# Power.net
KiCad netlist of a schematic drawn in Altium Designer
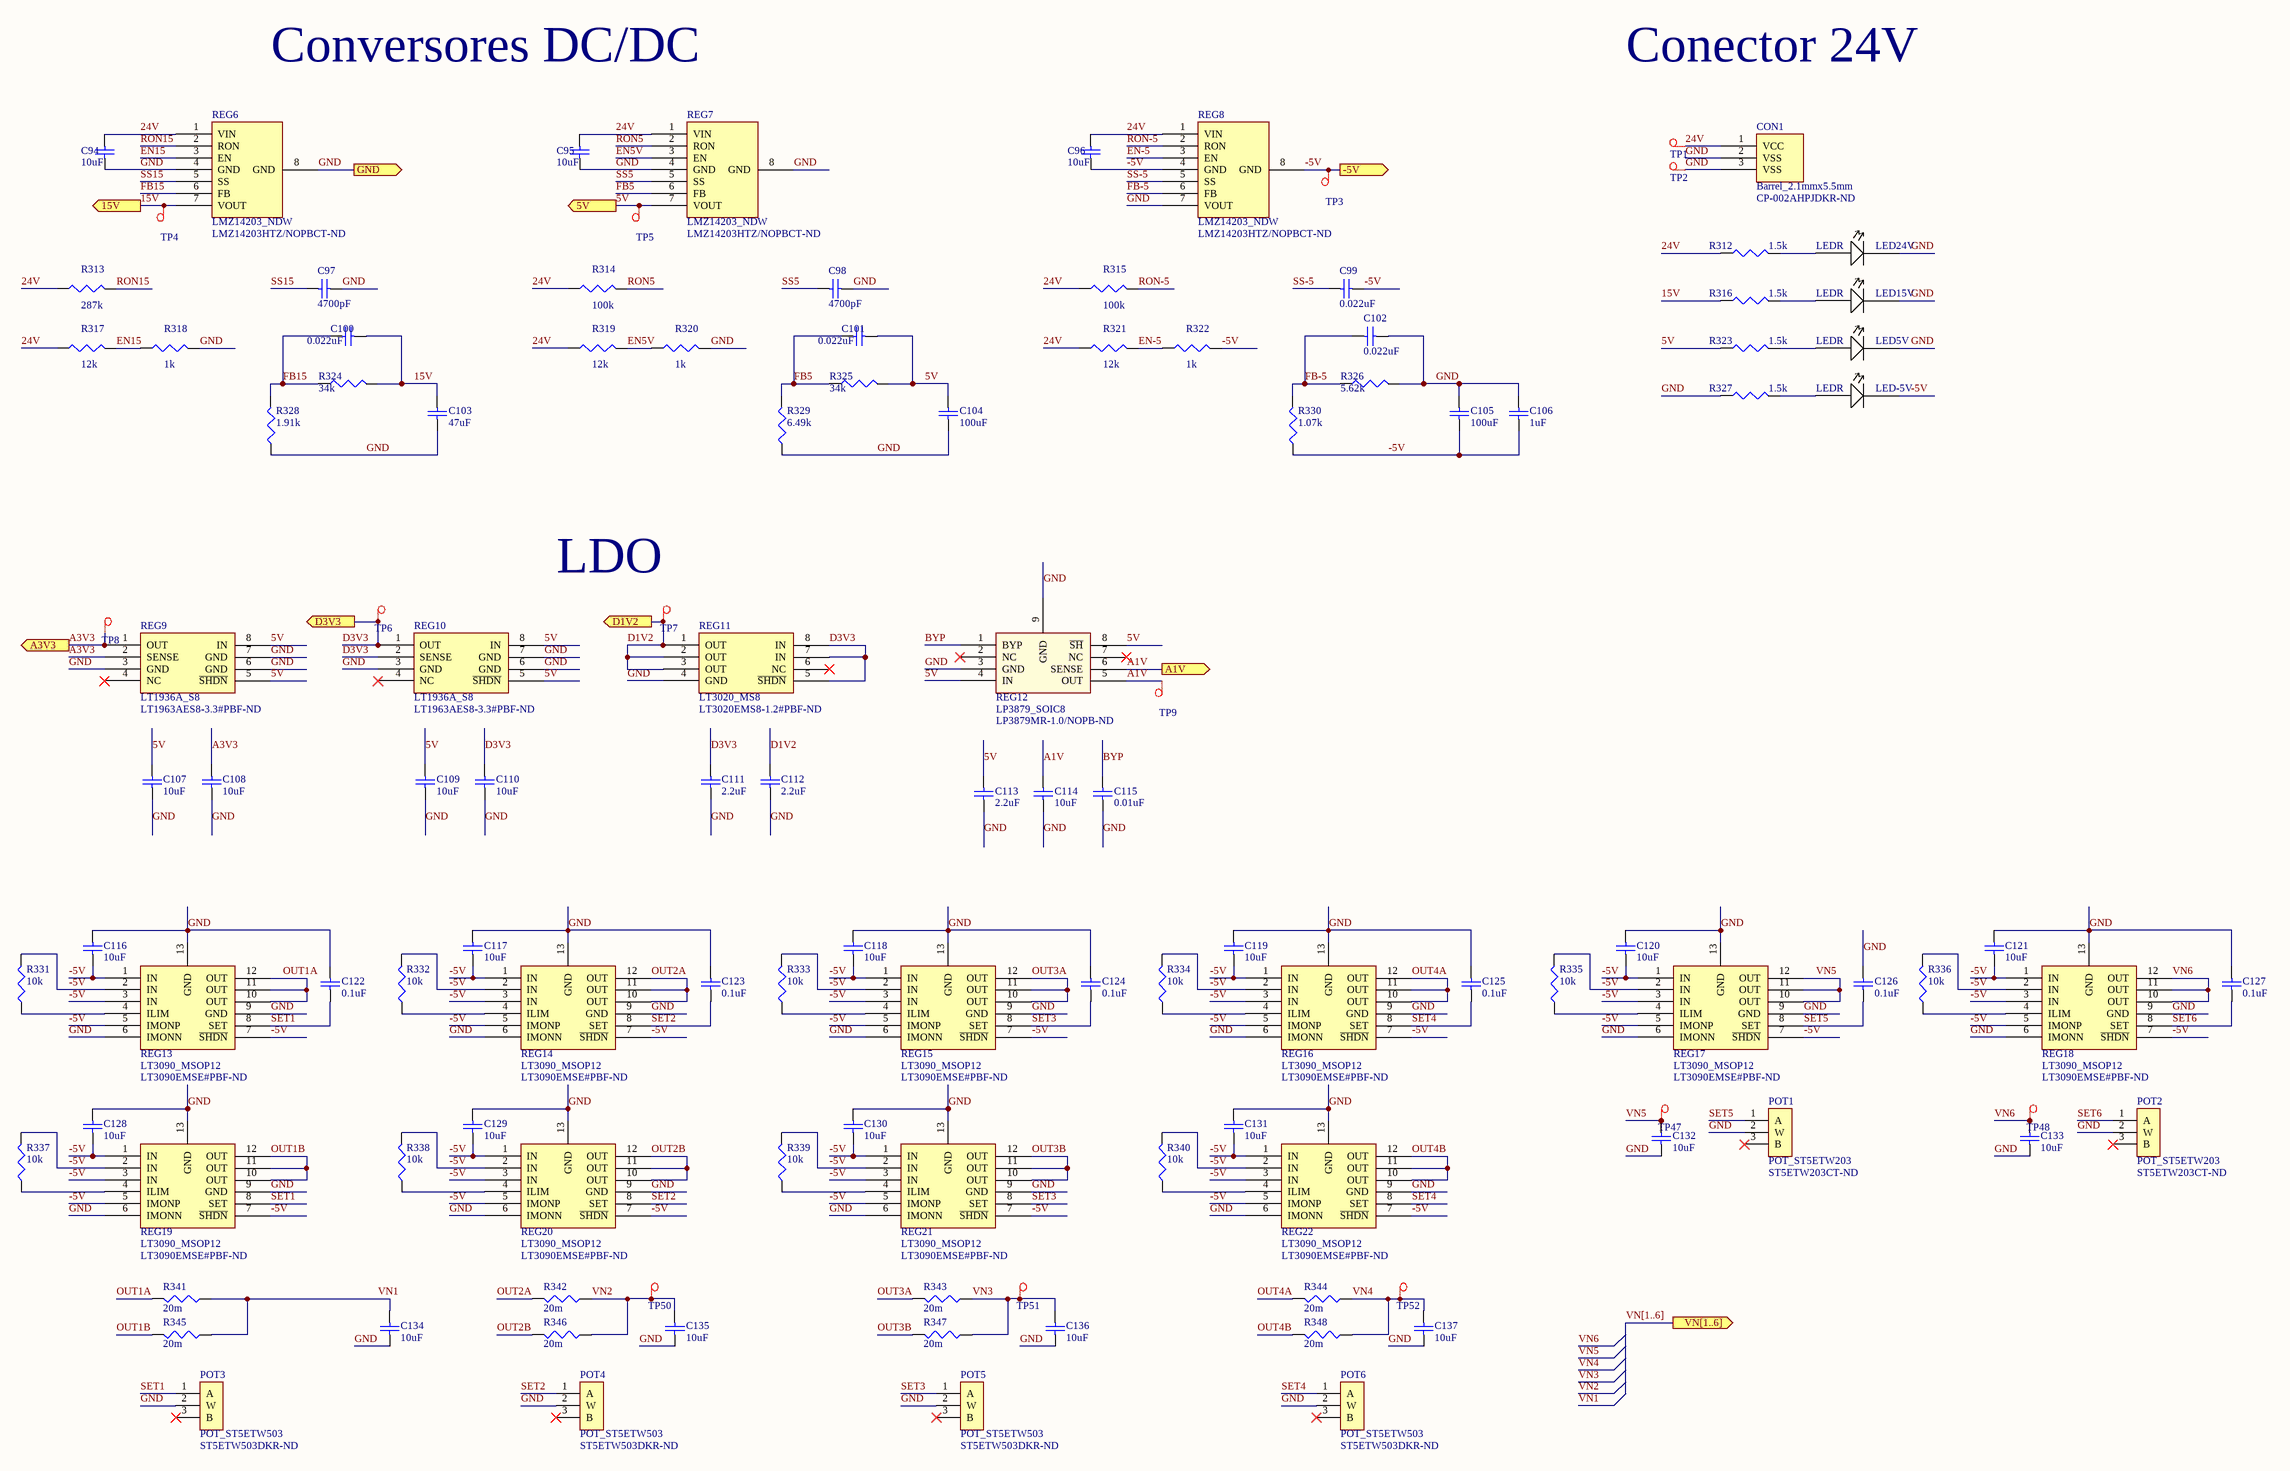
[diagram p0: Power.SchDoc]

(export (version "E")
  (design (tool "Eeschema 10.0.6"))
  (components
    (comp (ref "C94")
      (value "10uF")
      (footprint "RES_1206")
      (description "Capacitor")
      (fields (field (name "Comment") "Cap") (field (name "PUBLISHER") "Altium Limited"))
      (libsource (lib "Miscellaneous Devices") (part "Cap"))
    )
    (comp (ref "C95")
      (value "10uF")
      (footprint "RES_1206")
      (description "Capacitor")
      (fields (field (name "Comment") "Cap") (field (name "PUBLISHER") "Altium Limited"))
      (libsource (lib "Miscellaneous Devices") (part "Cap"))
    )
    (comp (ref "C96")
      (value "10uF")
      (footprint "RES_1206")
      (description "Capacitor")
      (fields (field (name "Comment") "Cap") (field (name "PUBLISHER") "Altium Limited"))
      (libsource (lib "Miscellaneous Devices") (part "Cap"))
    )
    (comp (ref "C97")
      (value "4700pF")
      (footprint "J1-0603")
      (description "Capacitor")
      (fields (field (name "Comment") "Cap") (field (name "PUBLISHER") "Altium Limited"))
      (libsource (lib "Miscellaneous Devices") (part "Cap"))
    )
    (comp (ref "C98")
      (value "4700pF")
      (footprint "J1-0603")
      (description "Capacitor")
      (fields (field (name "Comment") "Cap") (field (name "PUBLISHER") "Altium Limited"))
      (libsource (lib "Miscellaneous Devices") (part "Cap"))
    )
    (comp (ref "C99")
      (value "0.022uF")
      (footprint "J1-0603")
      (description "Capacitor")
      (fields (field (name "Comment") "Cap") (field (name "PUBLISHER") "Altium Limited"))
      (libsource (lib "Miscellaneous Devices") (part "Cap"))
    )
    (comp (ref "C100")
      (value "0.022uF")
      (footprint "J1-0603")
      (description "Capacitor")
      (fields (field (name "Comment") "Cap") (field (name "PUBLISHER") "Altium Limited"))
      (libsource (lib "Miscellaneous Devices") (part "Cap"))
    )
    (comp (ref "C101")
      (value "0.022uF")
      (footprint "J1-0603")
      (description "Capacitor")
      (fields (field (name "Comment") "Cap") (field (name "PUBLISHER") "Altium Limited"))
      (libsource (lib "Miscellaneous Devices") (part "Cap"))
    )
    (comp (ref "C102")
      (value "0.022uF")
      (footprint "J1-0603")
      (description "Capacitor")
      (fields (field (name "Comment") "Cap") (field (name "PUBLISHER") "Altium Limited"))
      (libsource (lib "Miscellaneous Devices") (part "Cap"))
    )
    (comp (ref "C103")
      (value "47uF")
      (footprint "RES_1206")
      (description "Capacitor")
      (fields (field (name "Comment") "Cap") (field (name "PUBLISHER") "Altium Limited"))
      (libsource (lib "Miscellaneous Devices") (part "Cap"))
    )
    (comp (ref "C104")
      (value "100uF")
      (footprint "J1-0603")
      (description "Capacitor")
      (fields (field (name "Comment") "Cap") (field (name "PUBLISHER") "Altium Limited"))
      (libsource (lib "Miscellaneous Devices") (part "Cap"))
    )
    (comp (ref "C105")
      (value "100uF")
      (footprint "J1-0603")
      (description "Capacitor")
      (fields (field (name "Comment") "Cap") (field (name "PUBLISHER") "Altium Limited"))
      (libsource (lib "Miscellaneous Devices") (part "Cap"))
    )
    (comp (ref "C106")
      (value "1uF")
      (footprint "J1-0603")
      (description "Capacitor")
      (fields (field (name "Comment") "Cap") (field (name "PUBLISHER") "Altium Limited"))
      (libsource (lib "Miscellaneous Devices") (part "Cap"))
    )
    (comp (ref "C107")
      (value "10uF")
      (footprint "RES_0805")
      (description "Capacitor")
      (fields (field (name "Comment") "Cap") (field (name "PUBLISHER") "Altium Limited"))
      (libsource (lib "Miscellaneous Devices") (part "Cap"))
    )
    (comp (ref "C108")
      (value "10uF")
      (footprint "RES_0805")
      (description "Capacitor")
      (fields (field (name "Comment") "Cap") (field (name "PUBLISHER") "Altium Limited"))
      (libsource (lib "Miscellaneous Devices") (part "Cap"))
    )
    (comp (ref "C109")
      (value "10uF")
      (footprint "RES_0805")
      (description "Capacitor")
      (fields (field (name "Comment") "Cap") (field (name "PUBLISHER") "Altium Limited"))
      (libsource (lib "Miscellaneous Devices") (part "Cap"))
    )
    (comp (ref "C110")
      (value "10uF")
      (footprint "RES_0805")
      (description "Capacitor")
      (fields (field (name "Comment") "Cap") (field (name "PUBLISHER") "Altium Limited"))
      (libsource (lib "Miscellaneous Devices") (part "Cap"))
    )
    (comp (ref "C111")
      (value "2.2uF")
      (footprint "J1-0603")
      (description "Capacitor")
      (fields (field (name "Comment") "Cap") (field (name "PUBLISHER") "Altium Limited"))
      (libsource (lib "Miscellaneous Devices") (part "Cap"))
    )
    (comp (ref "C112")
      (value "2.2uF")
      (footprint "J1-0603")
      (description "Capacitor")
      (fields (field (name "Comment") "Cap") (field (name "PUBLISHER") "Altium Limited"))
      (libsource (lib "Miscellaneous Devices") (part "Cap"))
    )
    (comp (ref "C113")
      (value "2.2uF")
      (footprint "J1-0603")
      (description "Capacitor")
      (fields (field (name "Comment") "Cap") (field (name "PUBLISHER") "Altium Limited"))
      (libsource (lib "Miscellaneous Devices") (part "Cap"))
    )
    (comp (ref "C114")
      (value "10uF")
      (footprint "RES_0805")
      (description "Capacitor")
      (fields (field (name "Comment") "Cap") (field (name "PUBLISHER") "Altium Limited"))
      (libsource (lib "Miscellaneous Devices") (part "Cap"))
    )
    (comp (ref "C115")
      (value "0.01uF")
      (footprint "J1-0603")
      (description "Capacitor")
      (fields (field (name "Comment") "Cap") (field (name "PUBLISHER") "Altium Limited"))
      (libsource (lib "Miscellaneous Devices") (part "Cap"))
    )
    (comp (ref "C116")
      (value "10uF")
      (footprint "RES_0805")
      (description "Capacitor")
      (fields (field (name "Comment") "Cap") (field (name "PUBLISHER") "Altium Limited"))
      (libsource (lib "Miscellaneous Devices") (part "Cap"))
    )
    (comp (ref "C117")
      (value "10uF")
      (footprint "RES_0805")
      (description "Capacitor")
      (fields (field (name "Comment") "Cap") (field (name "PUBLISHER") "Altium Limited"))
      (libsource (lib "Miscellaneous Devices") (part "Cap"))
    )
    (comp (ref "C118")
      (value "10uF")
      (footprint "RES_0805")
      (description "Capacitor")
      (fields (field (name "Comment") "Cap") (field (name "PUBLISHER") "Altium Limited"))
      (libsource (lib "Miscellaneous Devices") (part "Cap"))
    )
    (comp (ref "C119")
      (value "10uF")
      (footprint "RES_0805")
      (description "Capacitor")
      (fields (field (name "Comment") "Cap") (field (name "PUBLISHER") "Altium Limited"))
      (libsource (lib "Miscellaneous Devices") (part "Cap"))
    )
    (comp (ref "C120")
      (value "10uF")
      (footprint "RES_0805")
      (description "Capacitor")
      (fields (field (name "Comment") "Cap") (field (name "PUBLISHER") "Altium Limited"))
      (libsource (lib "Miscellaneous Devices") (part "Cap"))
    )
    (comp (ref "C121")
      (value "10uF")
      (footprint "RES_0805")
      (description "Capacitor")
      (fields (field (name "Comment") "Cap") (field (name "PUBLISHER") "Altium Limited"))
      (libsource (lib "Miscellaneous Devices") (part "Cap"))
    )
    (comp (ref "C122")
      (value "0.1uF")
      (footprint "J1-0603")
      (description "Capacitor")
      (fields (field (name "Comment") "Cap") (field (name "PUBLISHER") "Altium Limited"))
      (libsource (lib "Miscellaneous Devices") (part "Cap"))
    )
    (comp (ref "C123")
      (value "0.1uF")
      (footprint "J1-0603")
      (description "Capacitor")
      (fields (field (name "Comment") "Cap") (field (name "PUBLISHER") "Altium Limited"))
      (libsource (lib "Miscellaneous Devices") (part "Cap"))
    )
    (comp (ref "C124")
      (value "0.1uF")
      (footprint "J1-0603")
      (description "Capacitor")
      (fields (field (name "Comment") "Cap") (field (name "PUBLISHER") "Altium Limited"))
      (libsource (lib "Miscellaneous Devices") (part "Cap"))
    )
    (comp (ref "C125")
      (value "0.1uF")
      (footprint "J1-0603")
      (description "Capacitor")
      (fields (field (name "Comment") "Cap") (field (name "PUBLISHER") "Altium Limited"))
      (libsource (lib "Miscellaneous Devices") (part "Cap"))
    )
    (comp (ref "C126")
      (value "0.1uF")
      (footprint "J1-0603")
      (description "Capacitor")
      (fields (field (name "Comment") "Cap") (field (name "PUBLISHER") "Altium Limited"))
      (libsource (lib "Miscellaneous Devices") (part "Cap"))
    )
    (comp (ref "C127")
      (value "0.1uF")
      (footprint "J1-0603")
      (description "Capacitor")
      (fields (field (name "Comment") "Cap") (field (name "PUBLISHER") "Altium Limited"))
      (libsource (lib "Miscellaneous Devices") (part "Cap"))
    )
    (comp (ref "C128")
      (value "10uF")
      (footprint "RES_0805")
      (description "Capacitor")
      (fields (field (name "Comment") "Cap") (field (name "PUBLISHER") "Altium Limited"))
      (libsource (lib "Miscellaneous Devices") (part "Cap"))
    )
    (comp (ref "C129")
      (value "10uF")
      (footprint "RES_0805")
      (description "Capacitor")
      (fields (field (name "Comment") "Cap") (field (name "PUBLISHER") "Altium Limited"))
      (libsource (lib "Miscellaneous Devices") (part "Cap"))
    )
    (comp (ref "C130")
      (value "10uF")
      (footprint "RES_0805")
      (description "Capacitor")
      (fields (field (name "Comment") "Cap") (field (name "PUBLISHER") "Altium Limited"))
      (libsource (lib "Miscellaneous Devices") (part "Cap"))
    )
    (comp (ref "C131")
      (value "10uF")
      (footprint "RES_0805")
      (description "Capacitor")
      (fields (field (name "Comment") "Cap") (field (name "PUBLISHER") "Altium Limited"))
      (libsource (lib "Miscellaneous Devices") (part "Cap"))
    )
    (comp (ref "C132")
      (value "10uF")
      (footprint "RES_0805")
      (description "Capacitor")
      (fields (field (name "Comment") "Cap") (field (name "PUBLISHER") "Altium Limited"))
      (libsource (lib "Miscellaneous Devices") (part "Cap"))
    )
    (comp (ref "C133")
      (value "10uF")
      (footprint "RES_0805")
      (description "Capacitor")
      (fields (field (name "Comment") "Cap") (field (name "PUBLISHER") "Altium Limited"))
      (libsource (lib "Miscellaneous Devices") (part "Cap"))
    )
    (comp (ref "C134")
      (value "10uF")
      (footprint "RES_0805")
      (description "Capacitor")
      (fields (field (name "Comment") "Cap") (field (name "PUBLISHER") "Altium Limited"))
      (libsource (lib "Miscellaneous Devices") (part "Cap"))
    )
    (comp (ref "C135")
      (value "10uF")
      (footprint "RES_0805")
      (description "Capacitor")
      (fields (field (name "Comment") "Cap") (field (name "PUBLISHER") "Altium Limited"))
      (libsource (lib "Miscellaneous Devices") (part "Cap"))
    )
    (comp (ref "C136")
      (value "10uF")
      (footprint "RES_0805")
      (description "Capacitor")
      (fields (field (name "Comment") "Cap") (field (name "PUBLISHER") "Altium Limited"))
      (libsource (lib "Miscellaneous Devices") (part "Cap"))
    )
    (comp (ref "C137")
      (value "10uF")
      (footprint "RES_0805")
      (description "Capacitor")
      (fields (field (name "Comment") "Cap") (field (name "PUBLISHER") "Altium Limited"))
      (libsource (lib "Miscellaneous Devices") (part "Cap"))
    )
    (comp (ref "CON1")
      (value "Barrel_2.1mmx5.5mm")
      (footprint "Barrel_2.1mmx5.5mm")
      (fields (field (name "SUPPLIER PART NUMBER 1") "CP-002AHPJDKR-ND"))
      (libsource (lib "Lib1") (part "Barrel_2.1mmx5.5mm"))
    )
    (comp (ref "LED-5V") (value "LEDR") (footprint "LED") (libsource (lib "Lib1") (part "LEDR")))
    (comp (ref "LED5V") (value "LEDR") (footprint "LED") (libsource (lib "Lib1") (part "LEDR")))
    (comp (ref "LED15V") (value "LEDR") (footprint "LED") (libsource (lib "Lib1") (part "LEDR")))
    (comp (ref "LED24V") (value "LEDR") (footprint "LED") (libsource (lib "Lib1") (part "LEDR")))
    (comp (ref "POT1")
      (value "POT_ST5ETW203")
      (footprint "POT_ST5ETW")
      (fields (field (name "SUPPLIER PART NUMBER 1") "ST5ETW203CT-ND"))
      (libsource (lib "Lib1") (part "POT_ST5ETW203"))
    )
    (comp (ref "POT2")
      (value "POT_ST5ETW203")
      (footprint "POT_ST5ETW")
      (fields (field (name "SUPPLIER PART NUMBER 1") "ST5ETW203CT-ND"))
      (libsource (lib "Lib1") (part "POT_ST5ETW203"))
    )
    (comp (ref "POT3")
      (value "POT_ST5ETW503")
      (footprint "POT_ST5ETW")
      (fields (field (name "SUPPLIER PART NUMBER 1") "ST5ETW503DKR-ND"))
      (libsource (lib "Lib1") (part "POT_ST5ETW503"))
    )
    (comp (ref "POT4")
      (value "POT_ST5ETW503")
      (footprint "POT_ST5ETW")
      (fields (field (name "SUPPLIER PART NUMBER 1") "ST5ETW503DKR-ND"))
      (libsource (lib "Lib1") (part "POT_ST5ETW503"))
    )
    (comp (ref "POT5")
      (value "POT_ST5ETW503")
      (footprint "POT_ST5ETW")
      (fields (field (name "SUPPLIER PART NUMBER 1") "ST5ETW503DKR-ND"))
      (libsource (lib "Lib1") (part "POT_ST5ETW503"))
    )
    (comp (ref "POT6")
      (value "POT_ST5ETW503")
      (footprint "POT_ST5ETW")
      (fields (field (name "SUPPLIER PART NUMBER 1") "ST5ETW503DKR-ND"))
      (libsource (lib "Lib1") (part "POT_ST5ETW503"))
    )
    (comp (ref "R312")
      (value "1.5k")
      (footprint "J1-0603")
      (description "Resistor")
      (fields (field (name "Comment") "Res3") (field (name "PUBLISHER") "Altium Limited"))
      (libsource (lib "Miscellaneous Devices") (part "Res3"))
    )
    (comp (ref "R313")
      (value "287k")
      (footprint "J1-0603")
      (description "Resistor")
      (fields (field (name "Comment") "Res3") (field (name "PUBLISHER") "Altium Limited"))
      (libsource (lib "Miscellaneous Devices") (part "Res3"))
    )
    (comp (ref "R314")
      (value "100k")
      (footprint "J1-0603")
      (description "Resistor")
      (fields (field (name "Comment") "Res3") (field (name "PUBLISHER") "Altium Limited"))
      (libsource (lib "Miscellaneous Devices") (part "Res3"))
    )
    (comp (ref "R315")
      (value "100k")
      (footprint "J1-0603")
      (description "Resistor")
      (fields (field (name "Comment") "Res3") (field (name "PUBLISHER") "Altium Limited"))
      (libsource (lib "Miscellaneous Devices") (part "Res3"))
    )
    (comp (ref "R316")
      (value "1.5k")
      (footprint "J1-0603")
      (description "Resistor")
      (fields (field (name "Comment") "Res3") (field (name "PUBLISHER") "Altium Limited"))
      (libsource (lib "Miscellaneous Devices") (part "Res3"))
    )
    (comp (ref "R317")
      (value "12k")
      (footprint "J1-0603")
      (description "Resistor")
      (fields (field (name "Comment") "Res3") (field (name "PUBLISHER") "Altium Limited"))
      (libsource (lib "Miscellaneous Devices") (part "Res3"))
    )
    (comp (ref "R318")
      (value "1k")
      (footprint "J1-0603")
      (description "Resistor")
      (fields (field (name "Comment") "Res3") (field (name "PUBLISHER") "Altium Limited"))
      (libsource (lib "Miscellaneous Devices") (part "Res3"))
    )
    (comp (ref "R319")
      (value "12k")
      (footprint "J1-0603")
      (description "Resistor")
      (fields (field (name "Comment") "Res3") (field (name "PUBLISHER") "Altium Limited"))
      (libsource (lib "Miscellaneous Devices") (part "Res3"))
    )
    (comp (ref "R320")
      (value "1k")
      (footprint "J1-0603")
      (description "Resistor")
      (fields (field (name "Comment") "Res3") (field (name "PUBLISHER") "Altium Limited"))
      (libsource (lib "Miscellaneous Devices") (part "Res3"))
    )
    (comp (ref "R321")
      (value "12k")
      (footprint "J1-0603")
      (description "Resistor")
      (fields (field (name "Comment") "Res3") (field (name "PUBLISHER") "Altium Limited"))
      (libsource (lib "Miscellaneous Devices") (part "Res3"))
    )
    (comp (ref "R322")
      (value "1k")
      (footprint "J1-0603")
      (description "Resistor")
      (fields (field (name "Comment") "Res3") (field (name "PUBLISHER") "Altium Limited"))
      (libsource (lib "Miscellaneous Devices") (part "Res3"))
    )
    (comp (ref "R323")
      (value "1.5k")
      (footprint "J1-0603")
      (description "Resistor")
      (fields (field (name "Comment") "Res3") (field (name "PUBLISHER") "Altium Limited"))
      (libsource (lib "Miscellaneous Devices") (part "Res3"))
    )
    (comp (ref "R324")
      (value "34k")
      (footprint "J1-0603")
      (description "Resistor")
      (fields (field (name "Comment") "Res3") (field (name "PUBLISHER") "Altium Limited"))
      (libsource (lib "Miscellaneous Devices") (part "Res3"))
    )
    (comp (ref "R325")
      (value "34k")
      (footprint "J1-0603")
      (description "Resistor")
      (fields (field (name "Comment") "Res3") (field (name "PUBLISHER") "Altium Limited"))
      (libsource (lib "Miscellaneous Devices") (part "Res3"))
    )
    (comp (ref "R326")
      (value "5.62k")
      (footprint "J1-0603")
      (description "Resistor")
      (fields (field (name "Comment") "Res3") (field (name "PUBLISHER") "Altium Limited"))
      (libsource (lib "Miscellaneous Devices") (part "Res3"))
    )
    (comp (ref "R327")
      (value "1.5k")
      (footprint "J1-0603")
      (description "Resistor")
      (fields (field (name "Comment") "Res3") (field (name "PUBLISHER") "Altium Limited"))
      (libsource (lib "Miscellaneous Devices") (part "Res3"))
    )
    (comp (ref "R328")
      (value "1.91k")
      (footprint "J1-0603")
      (description "Resistor")
      (fields (field (name "Comment") "Res3") (field (name "PUBLISHER") "Altium Limited"))
      (libsource (lib "Miscellaneous Devices") (part "Res3"))
    )
    (comp (ref "R329")
      (value "6.49k")
      (footprint "J1-0603")
      (description "Resistor")
      (fields (field (name "Comment") "Res3") (field (name "PUBLISHER") "Altium Limited"))
      (libsource (lib "Miscellaneous Devices") (part "Res3"))
    )
    (comp (ref "R330")
      (value "1.07k")
      (footprint "J1-0603")
      (description "Resistor")
      (fields (field (name "Comment") "Res3") (field (name "PUBLISHER") "Altium Limited"))
      (libsource (lib "Miscellaneous Devices") (part "Res3"))
    )
    (comp (ref "R331")
      (value "10k")
      (footprint "J1-0603")
      (description "Resistor")
      (fields (field (name "Comment") "Res3") (field (name "PUBLISHER") "Altium Limited"))
      (libsource (lib "Miscellaneous Devices") (part "Res3"))
    )
    (comp (ref "R332")
      (value "10k")
      (footprint "J1-0603")
      (description "Resistor")
      (fields (field (name "Comment") "Res3") (field (name "PUBLISHER") "Altium Limited"))
      (libsource (lib "Miscellaneous Devices") (part "Res3"))
    )
    (comp (ref "R333")
      (value "10k")
      (footprint "J1-0603")
      (description "Resistor")
      (fields (field (name "Comment") "Res3") (field (name "PUBLISHER") "Altium Limited"))
      (libsource (lib "Miscellaneous Devices") (part "Res3"))
    )
    (comp (ref "R334")
      (value "10k")
      (footprint "J1-0603")
      (description "Resistor")
      (fields (field (name "Comment") "Res3") (field (name "PUBLISHER") "Altium Limited"))
      (libsource (lib "Miscellaneous Devices") (part "Res3"))
    )
    (comp (ref "R335")
      (value "10k")
      (footprint "J1-0603")
      (description "Resistor")
      (fields (field (name "Comment") "Res3") (field (name "PUBLISHER") "Altium Limited"))
      (libsource (lib "Miscellaneous Devices") (part "Res3"))
    )
    (comp (ref "R336")
      (value "10k")
      (footprint "J1-0603")
      (description "Resistor")
      (fields (field (name "Comment") "Res3") (field (name "PUBLISHER") "Altium Limited"))
      (libsource (lib "Miscellaneous Devices") (part "Res3"))
    )
    (comp (ref "R337")
      (value "10k")
      (footprint "J1-0603")
      (description "Resistor")
      (fields (field (name "Comment") "Res3") (field (name "PUBLISHER") "Altium Limited"))
      (libsource (lib "Miscellaneous Devices") (part "Res3"))
    )
    (comp (ref "R338")
      (value "10k")
      (footprint "J1-0603")
      (description "Resistor")
      (fields (field (name "Comment") "Res3") (field (name "PUBLISHER") "Altium Limited"))
      (libsource (lib "Miscellaneous Devices") (part "Res3"))
    )
    (comp (ref "R339")
      (value "10k")
      (footprint "J1-0603")
      (description "Resistor")
      (fields (field (name "Comment") "Res3") (field (name "PUBLISHER") "Altium Limited"))
      (libsource (lib "Miscellaneous Devices") (part "Res3"))
    )
    (comp (ref "R340")
      (value "10k")
      (footprint "J1-0603")
      (description "Resistor")
      (fields (field (name "Comment") "Res3") (field (name "PUBLISHER") "Altium Limited"))
      (libsource (lib "Miscellaneous Devices") (part "Res3"))
    )
    (comp (ref "R341")
      (value "20m")
      (footprint "J1-0603")
      (description "Resistor")
      (fields (field (name "Comment") "Res3") (field (name "PUBLISHER") "Altium Limited"))
      (libsource (lib "Miscellaneous Devices") (part "Res3"))
    )
    (comp (ref "R342")
      (value "20m")
      (footprint "J1-0603")
      (description "Resistor")
      (fields (field (name "Comment") "Res3") (field (name "PUBLISHER") "Altium Limited"))
      (libsource (lib "Miscellaneous Devices") (part "Res3"))
    )
    (comp (ref "R343")
      (value "20m")
      (footprint "J1-0603")
      (description "Resistor")
      (fields (field (name "Comment") "Res3") (field (name "PUBLISHER") "Altium Limited"))
      (libsource (lib "Miscellaneous Devices") (part "Res3"))
    )
    (comp (ref "R344")
      (value "20m")
      (footprint "J1-0603")
      (description "Resistor")
      (fields (field (name "Comment") "Res3") (field (name "PUBLISHER") "Altium Limited"))
      (libsource (lib "Miscellaneous Devices") (part "Res3"))
    )
    (comp (ref "R345")
      (value "20m")
      (footprint "J1-0603")
      (description "Resistor")
      (fields (field (name "Comment") "Res3") (field (name "PUBLISHER") "Altium Limited"))
      (libsource (lib "Miscellaneous Devices") (part "Res3"))
    )
    (comp (ref "R346")
      (value "20m")
      (footprint "J1-0603")
      (description "Resistor")
      (fields (field (name "Comment") "Res3") (field (name "PUBLISHER") "Altium Limited"))
      (libsource (lib "Miscellaneous Devices") (part "Res3"))
    )
    (comp (ref "R347")
      (value "20m")
      (footprint "J1-0603")
      (description "Resistor")
      (fields (field (name "Comment") "Res3") (field (name "PUBLISHER") "Altium Limited"))
      (libsource (lib "Miscellaneous Devices") (part "Res3"))
    )
    (comp (ref "R348")
      (value "20m")
      (footprint "J1-0603")
      (description "Resistor")
      (fields (field (name "Comment") "Res3") (field (name "PUBLISHER") "Altium Limited"))
      (libsource (lib "Miscellaneous Devices") (part "Res3"))
    )
    (comp (ref "REG6")
      (value "LMZ14203_NDW")
      (footprint "LMZ14203_NDW")
      (fields (field (name "SUPPLIER PART NUMBER 1") "LMZ14203HTZ/NOPBCT-ND"))
      (libsource (lib "Lib1") (part "LMZ14203_NDW"))
    )
    (comp (ref "REG7")
      (value "LMZ14203_NDW")
      (footprint "LMZ14203_NDW")
      (fields (field (name "SUPPLIER PART NUMBER 1") "LMZ14203HTZ/NOPBCT-ND"))
      (libsource (lib "Lib1") (part "LMZ14203_NDW"))
    )
    (comp (ref "REG8")
      (value "LMZ14203_NDW")
      (footprint "LMZ14203_NDW")
      (fields (field (name "SUPPLIER PART NUMBER 1") "LMZ14203HTZ/NOPBCT-ND"))
      (libsource (lib "Lib1") (part "LMZ14203_NDW"))
    )
    (comp (ref "REG9")
      (value "LT1936A_S8")
      (footprint "LT1936A_S8")
      (fields (field (name "SUPPLIER PART NUMBER 1") "LT1963AES8-3.3#PBF-ND"))
      (libsource (lib "Lib1") (part "LT1936A_S8"))
    )
    (comp (ref "REG10")
      (value "LT1936A_S8")
      (footprint "LT1936A_S8")
      (fields (field (name "SUPPLIER PART NUMBER 1") "LT1963AES8-3.3#PBF-ND"))
      (libsource (lib "Lib1") (part "LT1936A_S8"))
    )
    (comp (ref "REG11")
      (value "LT3020_MS8")
      (footprint "LT3020_MS8")
      (fields (field (name "SUPPLIER PART NUMBER 1") "LT3020EMS8-1.2#PBF-ND"))
      (libsource (lib "Lib1") (part "LT3020_MS8"))
    )
    (comp (ref "REG12")
      (value "LP3879_SOIC8")
      (footprint "LP3879_SOIC8")
      (fields (field (name "SUPPLIER PART NUMBER 1") "LP3879MR-1.0/NOPB-ND"))
      (libsource (lib "Lib1") (part "LP3879_SOIC8"))
    )
    (comp (ref "REG13")
      (value "LT3090_MSOP12")
      (footprint "LT3090_MSOP12")
      (fields (field (name "SUPPLIER PART NUMBER 1") "LT3090EMSE#PBF-ND"))
      (libsource (lib "Lib1") (part "LT3090_MSOP12"))
    )
    (comp (ref "REG14")
      (value "LT3090_MSOP12")
      (footprint "LT3090_MSOP12")
      (fields (field (name "SUPPLIER PART NUMBER 1") "LT3090EMSE#PBF-ND"))
      (libsource (lib "Lib1") (part "LT3090_MSOP12"))
    )
    (comp (ref "REG15")
      (value "LT3090_MSOP12")
      (footprint "LT3090_MSOP12")
      (fields (field (name "SUPPLIER PART NUMBER 1") "LT3090EMSE#PBF-ND"))
      (libsource (lib "Lib1") (part "LT3090_MSOP12"))
    )
    (comp (ref "REG16")
      (value "LT3090_MSOP12")
      (footprint "LT3090_MSOP12")
      (fields (field (name "SUPPLIER PART NUMBER 1") "LT3090EMSE#PBF-ND"))
      (libsource (lib "Lib1") (part "LT3090_MSOP12"))
    )
    (comp (ref "REG17")
      (value "LT3090_MSOP12")
      (footprint "LT3090_MSOP12")
      (fields (field (name "SUPPLIER PART NUMBER 1") "LT3090EMSE#PBF-ND"))
      (libsource (lib "Lib1") (part "LT3090_MSOP12"))
    )
    (comp (ref "REG18")
      (value "LT3090_MSOP12")
      (footprint "LT3090_MSOP12")
      (fields (field (name "SUPPLIER PART NUMBER 1") "LT3090EMSE#PBF-ND"))
      (libsource (lib "Lib1") (part "LT3090_MSOP12"))
    )
    (comp (ref "REG19")
      (value "LT3090_MSOP12")
      (footprint "LT3090_MSOP12")
      (fields (field (name "SUPPLIER PART NUMBER 1") "LT3090EMSE#PBF-ND"))
      (libsource (lib "Lib1") (part "LT3090_MSOP12"))
    )
    (comp (ref "REG20")
      (value "LT3090_MSOP12")
      (footprint "LT3090_MSOP12")
      (fields (field (name "SUPPLIER PART NUMBER 1") "LT3090EMSE#PBF-ND"))
      (libsource (lib "Lib1") (part "LT3090_MSOP12"))
    )
    (comp (ref "REG21")
      (value "LT3090_MSOP12")
      (footprint "LT3090_MSOP12")
      (fields (field (name "SUPPLIER PART NUMBER 1") "LT3090EMSE#PBF-ND"))
      (libsource (lib "Lib1") (part "LT3090_MSOP12"))
    )
    (comp (ref "REG22")
      (value "LT3090_MSOP12")
      (footprint "LT3090_MSOP12")
      (fields (field (name "SUPPLIER PART NUMBER 1") "LT3090EMSE#PBF-ND"))
      (libsource (lib "Lib1") (part "LT3090_MSOP12"))
    )
    (comp (ref "TP1")
      (value "Test Point")
      (footprint "TestPoint")
      (libsource (lib "Lib1") (part "Test Point"))
    )
    (comp (ref "TP2")
      (value "Test Point")
      (footprint "TestPoint")
      (libsource (lib "Lib1") (part "Test Point"))
    )
    (comp (ref "TP3")
      (value "Test Point")
      (footprint "TestPoint")
      (libsource (lib "Lib1") (part "Test Point"))
    )
    (comp (ref "TP4")
      (value "Test Point")
      (footprint "TestPoint")
      (libsource (lib "Lib1") (part "Test Point"))
    )
    (comp (ref "TP5")
      (value "Test Point")
      (footprint "TestPoint")
      (libsource (lib "Lib1") (part "Test Point"))
    )
    (comp (ref "TP6")
      (value "Test Point")
      (footprint "TestPoint")
      (libsource (lib "Lib1") (part "Test Point"))
    )
    (comp (ref "TP7")
      (value "Test Point")
      (footprint "TestPoint")
      (libsource (lib "Lib1") (part "Test Point"))
    )
    (comp (ref "TP8")
      (value "Test Point")
      (footprint "TestPoint")
      (libsource (lib "Lib1") (part "Test Point"))
    )
    (comp (ref "TP9")
      (value "Test Point")
      (footprint "TestPoint")
      (libsource (lib "Lib1") (part "Test Point"))
    )
    (comp (ref "TP47")
      (value "Test Point")
      (footprint "TestPoint")
      (libsource (lib "Lib1") (part "Test Point"))
    )
    (comp (ref "TP48")
      (value "Test Point")
      (footprint "TestPoint")
      (libsource (lib "Lib1") (part "Test Point"))
    )
    (comp (ref "TP50")
      (value "Test Point")
      (footprint "TestPoint")
      (libsource (lib "Lib1") (part "Test Point"))
    )
    (comp (ref "TP51")
      (value "Test Point")
      (footprint "TestPoint")
      (libsource (lib "Lib1") (part "Test Point"))
    )
    (comp (ref "TP52")
      (value "Test Point")
      (footprint "TestPoint")
      (libsource (lib "Lib1") (part "Test Point"))
    )
  )
  (nets
    (net (code "1") (name "/-5V") (class "Default")
      (node (ref "C105") (pin "2") (pinfunction "2_2") (pintype "passive"))
      (node (ref "C106") (pin "2") (pinfunction "2_2") (pintype "passive"))
      (node (ref "C116") (pin "2") (pinfunction "2_2") (pintype "passive"))
      (node (ref "C117") (pin "2") (pinfunction "2_2") (pintype "passive"))
      (node (ref "C118") (pin "2") (pinfunction "2_2") (pintype "passive"))
      (node (ref "C119") (pin "2") (pinfunction "2_2") (pintype "passive"))
      (node (ref "C120") (pin "2") (pinfunction "2_2") (pintype "passive"))
      (node (ref "C121") (pin "2") (pinfunction "2_2") (pintype "passive"))
      (node (ref "C128") (pin "2") (pinfunction "2_2") (pintype "passive"))
      (node (ref "C129") (pin "2") (pinfunction "2_2") (pintype "passive"))
      (node (ref "C130") (pin "2") (pinfunction "2_2") (pintype "passive"))
      (node (ref "C131") (pin "2") (pinfunction "2_2") (pintype "passive"))
      (node (ref "C96") (pin "1") (pinfunction "1_1") (pintype "passive"))
      (node (ref "C99") (pin "1") (pinfunction "1_1") (pintype "passive"))
      (node (ref "LED-5V") (pin "2") (pinfunction "2_2") (pintype "passive"))
      (node (ref "R322") (pin "2") (pinfunction "2_2") (pintype "passive"))
      (node (ref "R330") (pin "1") (pinfunction "1_1") (pintype "passive"))
      (node (ref "R331") (pin "2") (pinfunction "2_2") (pintype "passive"))
      (node (ref "R332") (pin "2") (pinfunction "2_2") (pintype "passive"))
      (node (ref "R333") (pin "2") (pinfunction "2_2") (pintype "passive"))
      (node (ref "R334") (pin "2") (pinfunction "2_2") (pintype "passive"))
      (node (ref "R335") (pin "2") (pinfunction "2_2") (pintype "passive"))
      (node (ref "R336") (pin "2") (pinfunction "2_2") (pintype "passive"))
      (node (ref "R337") (pin "2") (pinfunction "2_2") (pintype "passive"))
      (node (ref "R338") (pin "2") (pinfunction "2_2") (pintype "passive"))
      (node (ref "R339") (pin "2") (pinfunction "2_2") (pintype "passive"))
      (node (ref "R340") (pin "2") (pinfunction "2_2") (pintype "passive"))
      (node (ref "REG13") (pin "1") (pinfunction "IN_1") (pintype "passive"))
      (node (ref "REG13") (pin "2") (pinfunction "IN_2") (pintype "passive"))
      (node (ref "REG13") (pin "3") (pinfunction "IN_3") (pintype "passive"))
      (node (ref "REG13") (pin "5") (pinfunction "IMONP_5") (pintype "passive"))
      (node (ref "REG13") (pin "7") (pinfunction "~{SHDN}_7") (pintype "passive"))
      (node (ref "REG14") (pin "1") (pinfunction "IN_1") (pintype "passive"))
      (node (ref "REG14") (pin "2") (pinfunction "IN_2") (pintype "passive"))
      (node (ref "REG14") (pin "3") (pinfunction "IN_3") (pintype "passive"))
      (node (ref "REG14") (pin "5") (pinfunction "IMONP_5") (pintype "passive"))
      (node (ref "REG14") (pin "7") (pinfunction "~{SHDN}_7") (pintype "passive"))
      (node (ref "REG15") (pin "1") (pinfunction "IN_1") (pintype "passive"))
      (node (ref "REG15") (pin "2") (pinfunction "IN_2") (pintype "passive"))
      (node (ref "REG15") (pin "3") (pinfunction "IN_3") (pintype "passive"))
      (node (ref "REG15") (pin "5") (pinfunction "IMONP_5") (pintype "passive"))
      (node (ref "REG15") (pin "7") (pinfunction "~{SHDN}_7") (pintype "passive"))
      (node (ref "REG16") (pin "1") (pinfunction "IN_1") (pintype "passive"))
      (node (ref "REG16") (pin "2") (pinfunction "IN_2") (pintype "passive"))
      (node (ref "REG16") (pin "3") (pinfunction "IN_3") (pintype "passive"))
      (node (ref "REG16") (pin "5") (pinfunction "IMONP_5") (pintype "passive"))
      (node (ref "REG16") (pin "7") (pinfunction "~{SHDN}_7") (pintype "passive"))
      (node (ref "REG17") (pin "1") (pinfunction "IN_1") (pintype "passive"))
      (node (ref "REG17") (pin "2") (pinfunction "IN_2") (pintype "passive"))
      (node (ref "REG17") (pin "3") (pinfunction "IN_3") (pintype "passive"))
      (node (ref "REG17") (pin "5") (pinfunction "IMONP_5") (pintype "passive"))
      (node (ref "REG17") (pin "7") (pinfunction "~{SHDN}_7") (pintype "passive"))
      (node (ref "REG18") (pin "1") (pinfunction "IN_1") (pintype "passive"))
      (node (ref "REG18") (pin "2") (pinfunction "IN_2") (pintype "passive"))
      (node (ref "REG18") (pin "3") (pinfunction "IN_3") (pintype "passive"))
      (node (ref "REG18") (pin "5") (pinfunction "IMONP_5") (pintype "passive"))
      (node (ref "REG18") (pin "7") (pinfunction "~{SHDN}_7") (pintype "passive"))
      (node (ref "REG19") (pin "1") (pinfunction "IN_1") (pintype "passive"))
      (node (ref "REG19") (pin "2") (pinfunction "IN_2") (pintype "passive"))
      (node (ref "REG19") (pin "3") (pinfunction "IN_3") (pintype "passive"))
      (node (ref "REG19") (pin "5") (pinfunction "IMONP_5") (pintype "passive"))
      (node (ref "REG19") (pin "7") (pinfunction "~{SHDN}_7") (pintype "passive"))
      (node (ref "REG20") (pin "1") (pinfunction "IN_1") (pintype "passive"))
      (node (ref "REG20") (pin "2") (pinfunction "IN_2") (pintype "passive"))
      (node (ref "REG20") (pin "3") (pinfunction "IN_3") (pintype "passive"))
      (node (ref "REG20") (pin "5") (pinfunction "IMONP_5") (pintype "passive"))
      (node (ref "REG20") (pin "7") (pinfunction "~{SHDN}_7") (pintype "passive"))
      (node (ref "REG21") (pin "1") (pinfunction "IN_1") (pintype "passive"))
      (node (ref "REG21") (pin "2") (pinfunction "IN_2") (pintype "passive"))
      (node (ref "REG21") (pin "3") (pinfunction "IN_3") (pintype "passive"))
      (node (ref "REG21") (pin "5") (pinfunction "IMONP_5") (pintype "passive"))
      (node (ref "REG21") (pin "7") (pinfunction "~{SHDN}_7") (pintype "passive"))
      (node (ref "REG22") (pin "1") (pinfunction "IN_1") (pintype "passive"))
      (node (ref "REG22") (pin "2") (pinfunction "IN_2") (pintype "passive"))
      (node (ref "REG22") (pin "3") (pinfunction "IN_3") (pintype "passive"))
      (node (ref "REG22") (pin "5") (pinfunction "IMONP_5") (pintype "passive"))
      (node (ref "REG22") (pin "7") (pinfunction "~{SHDN}_7") (pintype "passive"))
      (node (ref "REG8") (pin "4") (pinfunction "GND_4") (pintype "passive"))
      (node (ref "REG8") (pin "8") (pinfunction "GND_8") (pintype "passive"))
      (node (ref "TP3") (pin "1") (pinfunction "TP_1") (pintype "passive"))
    )
    (net (code "2") (name "/5V") (class "Default")
      (node (ref "C101") (pin "1") (pinfunction "1_1") (pintype "passive"))
      (node (ref "C104") (pin "1") (pinfunction "1_1") (pintype "passive"))
      (node (ref "C107") (pin "1") (pinfunction "1_1") (pintype "passive"))
      (node (ref "C109") (pin "1") (pinfunction "1_1") (pintype "passive"))
      (node (ref "C113") (pin "1") (pinfunction "1_1") (pintype "passive"))
      (node (ref "R323") (pin "1") (pinfunction "1_1") (pintype "passive"))
      (node (ref "R325") (pin "2") (pinfunction "2_2") (pintype "passive"))
      (node (ref "REG10") (pin "5") (pinfunction "~{SHDN}_5") (pintype "passive"))
      (node (ref "REG10") (pin "8") (pinfunction "IN_8") (pintype "passive"))
      (node (ref "REG12") (pin "4") (pinfunction "IN_4") (pintype "passive"))
      (node (ref "REG12") (pin "8") (pinfunction "~{SH}_8") (pintype "passive"))
      (node (ref "REG7") (pin "7") (pinfunction "VOUT_7") (pintype "passive"))
      (node (ref "REG9") (pin "5") (pinfunction "~{SHDN}_5") (pintype "passive"))
      (node (ref "REG9") (pin "8") (pinfunction "IN_8") (pintype "passive"))
      (node (ref "TP5") (pin "1") (pinfunction "TP_1") (pintype "passive"))
    )
    (net (code "3") (name "/15V") (class "Default")
      (node (ref "C100") (pin "1") (pinfunction "1_1") (pintype "passive"))
      (node (ref "C103") (pin "1") (pinfunction "1_1") (pintype "passive"))
      (node (ref "R316") (pin "1") (pinfunction "1_1") (pintype "passive"))
      (node (ref "R324") (pin "2") (pinfunction "2_2") (pintype "passive"))
      (node (ref "REG6") (pin "7") (pinfunction "VOUT_7") (pintype "passive"))
      (node (ref "TP4") (pin "1") (pinfunction "TP_1") (pintype "passive"))
    )
    (net (code "4") (name "/24V") (class "Default")
      (node (ref "C94") (pin "2") (pinfunction "2_2") (pintype "passive"))
      (node (ref "C95") (pin "2") (pinfunction "2_2") (pintype "passive"))
      (node (ref "C96") (pin "2") (pinfunction "2_2") (pintype "passive"))
      (node (ref "CON1") (pin "1") (pinfunction "VCC_1") (pintype "passive"))
      (node (ref "R312") (pin "1") (pinfunction "1_1") (pintype "passive"))
      (node (ref "R313") (pin "1") (pinfunction "1_1") (pintype "passive"))
      (node (ref "R314") (pin "1") (pinfunction "1_1") (pintype "passive"))
      (node (ref "R315") (pin "1") (pinfunction "1_1") (pintype "passive"))
      (node (ref "R317") (pin "1") (pinfunction "1_1") (pintype "passive"))
      (node (ref "R319") (pin "1") (pinfunction "1_1") (pintype "passive"))
      (node (ref "R321") (pin "1") (pinfunction "1_1") (pintype "passive"))
      (node (ref "REG6") (pin "1") (pinfunction "VIN_1") (pintype "passive"))
      (node (ref "REG7") (pin "1") (pinfunction "VIN_1") (pintype "passive"))
      (node (ref "REG8") (pin "1") (pinfunction "VIN_1") (pintype "passive"))
      (node (ref "TP1") (pin "1") (pinfunction "TP_1") (pintype "passive"))
    )
    (net (code "5") (name "/A1V") (class "Default")
      (node (ref "C114") (pin "1") (pinfunction "1_1") (pintype "passive"))
      (node (ref "REG12") (pin "5") (pinfunction "OUT_5") (pintype "passive"))
      (node (ref "REG12") (pin "6") (pinfunction "SENSE_6") (pintype "passive"))
      (node (ref "TP9") (pin "1") (pinfunction "TP_1") (pintype "passive"))
    )
    (net (code "6") (name "/A3V3") (class "Default")
      (node (ref "C108") (pin "1") (pinfunction "1_1") (pintype "passive"))
      (node (ref "REG9") (pin "1") (pinfunction "OUT_1") (pintype "passive"))
      (node (ref "REG9") (pin "2") (pinfunction "SENSE_2") (pintype "passive"))
      (node (ref "TP8") (pin "1") (pinfunction "TP_1") (pintype "passive"))
    )
    (net (code "7") (name "/BYP") (class "Default")
      (node (ref "C115") (pin "1") (pinfunction "1_1") (pintype "passive"))
      (node (ref "REG12") (pin "1") (pinfunction "BYP_1") (pintype "passive"))
    )
    (net (code "8") (name "/D1V2") (class "Default")
      (node (ref "C112") (pin "1") (pinfunction "1_1") (pintype "passive"))
      (node (ref "REG11") (pin "1") (pinfunction "OUT_1") (pintype "passive"))
      (node (ref "REG11") (pin "2") (pinfunction "OUT_2") (pintype "passive"))
      (node (ref "REG11") (pin "3") (pinfunction "OUT_3") (pintype "passive"))
      (node (ref "TP7") (pin "1") (pinfunction "TP_1") (pintype "passive"))
    )
    (net (code "9") (name "/D3V3") (class "Default")
      (node (ref "C110") (pin "1") (pinfunction "1_1") (pintype "passive"))
      (node (ref "C111") (pin "1") (pinfunction "1_1") (pintype "passive"))
      (node (ref "REG10") (pin "1") (pinfunction "OUT_1") (pintype "passive"))
      (node (ref "REG10") (pin "2") (pinfunction "SENSE_2") (pintype "passive"))
      (node (ref "REG11") (pin "5") (pinfunction "~{SHDN}_5") (pintype "passive"))
      (node (ref "REG11") (pin "7") (pinfunction "IN_7") (pintype "passive"))
      (node (ref "REG11") (pin "8") (pinfunction "IN_8") (pintype "passive"))
      (node (ref "TP6") (pin "1") (pinfunction "TP_1") (pintype "passive"))
    )
    (net (code "10") (name "/EN-5") (class "Default")
      (node (ref "R321") (pin "2") (pinfunction "2_2") (pintype "passive"))
      (node (ref "R322") (pin "1") (pinfunction "1_1") (pintype "passive"))
      (node (ref "REG8") (pin "3") (pinfunction "EN_3") (pintype "passive"))
    )
    (net (code "11") (name "/EN5V") (class "Default")
      (node (ref "R319") (pin "2") (pinfunction "2_2") (pintype "passive"))
      (node (ref "R320") (pin "1") (pinfunction "1_1") (pintype "passive"))
      (node (ref "REG7") (pin "3") (pinfunction "EN_3") (pintype "passive"))
    )
    (net (code "12") (name "/EN15") (class "Default")
      (node (ref "R317") (pin "2") (pinfunction "2_2") (pintype "passive"))
      (node (ref "R318") (pin "1") (pinfunction "1_1") (pintype "passive"))
      (node (ref "REG6") (pin "3") (pinfunction "EN_3") (pintype "passive"))
    )
    (net (code "13") (name "/FB-5") (class "Default")
      (node (ref "C102") (pin "2") (pinfunction "2_2") (pintype "passive"))
      (node (ref "R326") (pin "1") (pinfunction "1_1") (pintype "passive"))
      (node (ref "R330") (pin "2") (pinfunction "2_2") (pintype "passive"))
      (node (ref "REG8") (pin "6") (pinfunction "FB_6") (pintype "passive"))
    )
    (net (code "14") (name "/FB5") (class "Default")
      (node (ref "C101") (pin "2") (pinfunction "2_2") (pintype "passive"))
      (node (ref "R325") (pin "1") (pinfunction "1_1") (pintype "passive"))
      (node (ref "R329") (pin "2") (pinfunction "2_2") (pintype "passive"))
      (node (ref "REG7") (pin "6") (pinfunction "FB_6") (pintype "passive"))
    )
    (net (code "15") (name "/FB15") (class "Default")
      (node (ref "C100") (pin "2") (pinfunction "2_2") (pintype "passive"))
      (node (ref "R324") (pin "1") (pinfunction "1_1") (pintype "passive"))
      (node (ref "R328") (pin "2") (pinfunction "2_2") (pintype "passive"))
      (node (ref "REG6") (pin "6") (pinfunction "FB_6") (pintype "passive"))
    )
    (net (code "16") (name "/GND") (class "Default")
      (node (ref "C102") (pin "1") (pinfunction "1_1") (pintype "passive"))
      (node (ref "C103") (pin "2") (pinfunction "2_2") (pintype "passive"))
      (node (ref "C104") (pin "2") (pinfunction "2_2") (pintype "passive"))
      (node (ref "C105") (pin "1") (pinfunction "1_1") (pintype "passive"))
      (node (ref "C106") (pin "1") (pinfunction "1_1") (pintype "passive"))
      (node (ref "C107") (pin "2") (pinfunction "2_2") (pintype "passive"))
      (node (ref "C108") (pin "2") (pinfunction "2_2") (pintype "passive"))
      (node (ref "C109") (pin "2") (pinfunction "2_2") (pintype "passive"))
      (node (ref "C110") (pin "2") (pinfunction "2_2") (pintype "passive"))
      (node (ref "C111") (pin "2") (pinfunction "2_2") (pintype "passive"))
      (node (ref "C112") (pin "2") (pinfunction "2_2") (pintype "passive"))
      (node (ref "C113") (pin "2") (pinfunction "2_2") (pintype "passive"))
      (node (ref "C114") (pin "2") (pinfunction "2_2") (pintype "passive"))
      (node (ref "C115") (pin "2") (pinfunction "2_2") (pintype "passive"))
      (node (ref "C116") (pin "1") (pinfunction "1_1") (pintype "passive"))
      (node (ref "C117") (pin "1") (pinfunction "1_1") (pintype "passive"))
      (node (ref "C118") (pin "1") (pinfunction "1_1") (pintype "passive"))
      (node (ref "C119") (pin "1") (pinfunction "1_1") (pintype "passive"))
      (node (ref "C120") (pin "1") (pinfunction "1_1") (pintype "passive"))
      (node (ref "C121") (pin "1") (pinfunction "1_1") (pintype "passive"))
      (node (ref "C122") (pin "1") (pinfunction "1_1") (pintype "passive"))
      (node (ref "C123") (pin "1") (pinfunction "1_1") (pintype "passive"))
      (node (ref "C124") (pin "1") (pinfunction "1_1") (pintype "passive"))
      (node (ref "C125") (pin "1") (pinfunction "1_1") (pintype "passive"))
      (node (ref "C126") (pin "1") (pinfunction "1_1") (pintype "passive"))
      (node (ref "C127") (pin "1") (pinfunction "1_1") (pintype "passive"))
      (node (ref "C128") (pin "1") (pinfunction "1_1") (pintype "passive"))
      (node (ref "C129") (pin "1") (pinfunction "1_1") (pintype "passive"))
      (node (ref "C130") (pin "1") (pinfunction "1_1") (pintype "passive"))
      (node (ref "C131") (pin "1") (pinfunction "1_1") (pintype "passive"))
      (node (ref "C132") (pin "2") (pinfunction "2_2") (pintype "passive"))
      (node (ref "C133") (pin "2") (pinfunction "2_2") (pintype "passive"))
      (node (ref "C134") (pin "2") (pinfunction "2_2") (pintype "passive"))
      (node (ref "C135") (pin "2") (pinfunction "2_2") (pintype "passive"))
      (node (ref "C136") (pin "2") (pinfunction "2_2") (pintype "passive"))
      (node (ref "C137") (pin "2") (pinfunction "2_2") (pintype "passive"))
      (node (ref "C94") (pin "1") (pinfunction "1_1") (pintype "passive"))
      (node (ref "C95") (pin "1") (pinfunction "1_1") (pintype "passive"))
      (node (ref "C97") (pin "1") (pinfunction "1_1") (pintype "passive"))
      (node (ref "C98") (pin "1") (pinfunction "1_1") (pintype "passive"))
      (node (ref "CON1") (pin "2") (pinfunction "VSS_2") (pintype "passive"))
      (node (ref "CON1") (pin "3") (pinfunction "VSS_3") (pintype "passive"))
      (node (ref "LED15V") (pin "2") (pinfunction "2_2") (pintype "passive"))
      (node (ref "LED24V") (pin "2") (pinfunction "2_2") (pintype "passive"))
      (node (ref "LED5V") (pin "2") (pinfunction "2_2") (pintype "passive"))
      (node (ref "POT1") (pin "2") (pinfunction "W_2") (pintype "passive"))
      (node (ref "POT2") (pin "2") (pinfunction "W_2") (pintype "passive"))
      (node (ref "POT3") (pin "2") (pinfunction "W_2") (pintype "passive"))
      (node (ref "POT4") (pin "2") (pinfunction "W_2") (pintype "passive"))
      (node (ref "POT5") (pin "2") (pinfunction "W_2") (pintype "passive"))
      (node (ref "POT6") (pin "2") (pinfunction "W_2") (pintype "passive"))
      (node (ref "R318") (pin "2") (pinfunction "2_2") (pintype "passive"))
      (node (ref "R320") (pin "2") (pinfunction "2_2") (pintype "passive"))
      (node (ref "R326") (pin "2") (pinfunction "2_2") (pintype "passive"))
      (node (ref "R327") (pin "1") (pinfunction "1_1") (pintype "passive"))
      (node (ref "R328") (pin "1") (pinfunction "1_1") (pintype "passive"))
      (node (ref "R329") (pin "1") (pinfunction "1_1") (pintype "passive"))
      (node (ref "REG10") (pin "3") (pinfunction "GND_3") (pintype "passive"))
      (node (ref "REG10") (pin "6") (pinfunction "GND_6") (pintype "passive"))
      (node (ref "REG10") (pin "7") (pinfunction "GND_7") (pintype "passive"))
      (node (ref "REG11") (pin "4") (pinfunction "GND_4") (pintype "passive"))
      (node (ref "REG12") (pin "3") (pinfunction "GND_3") (pintype "passive"))
      (node (ref "REG12") (pin "9") (pinfunction "GND_9") (pintype "passive"))
      (node (ref "REG13") (pin "13") (pinfunction "GND_13") (pintype "passive"))
      (node (ref "REG13") (pin "6") (pinfunction "IMONN_6") (pintype "passive"))
      (node (ref "REG13") (pin "9") (pinfunction "GND_9") (pintype "passive"))
      (node (ref "REG14") (pin "13") (pinfunction "GND_13") (pintype "passive"))
      (node (ref "REG14") (pin "6") (pinfunction "IMONN_6") (pintype "passive"))
      (node (ref "REG14") (pin "9") (pinfunction "GND_9") (pintype "passive"))
      (node (ref "REG15") (pin "13") (pinfunction "GND_13") (pintype "passive"))
      (node (ref "REG15") (pin "6") (pinfunction "IMONN_6") (pintype "passive"))
      (node (ref "REG15") (pin "9") (pinfunction "GND_9") (pintype "passive"))
      (node (ref "REG16") (pin "13") (pinfunction "GND_13") (pintype "passive"))
      (node (ref "REG16") (pin "6") (pinfunction "IMONN_6") (pintype "passive"))
      (node (ref "REG16") (pin "9") (pinfunction "GND_9") (pintype "passive"))
      (node (ref "REG17") (pin "13") (pinfunction "GND_13") (pintype "passive"))
      (node (ref "REG17") (pin "6") (pinfunction "IMONN_6") (pintype "passive"))
      (node (ref "REG17") (pin "9") (pinfunction "GND_9") (pintype "passive"))
      (node (ref "REG18") (pin "13") (pinfunction "GND_13") (pintype "passive"))
      (node (ref "REG18") (pin "6") (pinfunction "IMONN_6") (pintype "passive"))
      (node (ref "REG18") (pin "9") (pinfunction "GND_9") (pintype "passive"))
      (node (ref "REG19") (pin "13") (pinfunction "GND_13") (pintype "passive"))
      (node (ref "REG19") (pin "6") (pinfunction "IMONN_6") (pintype "passive"))
      (node (ref "REG19") (pin "9") (pinfunction "GND_9") (pintype "passive"))
      (node (ref "REG20") (pin "13") (pinfunction "GND_13") (pintype "passive"))
      (node (ref "REG20") (pin "6") (pinfunction "IMONN_6") (pintype "passive"))
      (node (ref "REG20") (pin "9") (pinfunction "GND_9") (pintype "passive"))
      (node (ref "REG21") (pin "13") (pinfunction "GND_13") (pintype "passive"))
      (node (ref "REG21") (pin "6") (pinfunction "IMONN_6") (pintype "passive"))
      (node (ref "REG21") (pin "9") (pinfunction "GND_9") (pintype "passive"))
      (node (ref "REG22") (pin "13") (pinfunction "GND_13") (pintype "passive"))
      (node (ref "REG22") (pin "6") (pinfunction "IMONN_6") (pintype "passive"))
      (node (ref "REG22") (pin "9") (pinfunction "GND_9") (pintype "passive"))
      (node (ref "REG6") (pin "4") (pinfunction "GND_4") (pintype "passive"))
      (node (ref "REG6") (pin "8") (pinfunction "GND_8") (pintype "passive"))
      (node (ref "REG7") (pin "4") (pinfunction "GND_4") (pintype "passive"))
      (node (ref "REG7") (pin "8") (pinfunction "GND_8") (pintype "passive"))
      (node (ref "REG8") (pin "7") (pinfunction "VOUT_7") (pintype "passive"))
      (node (ref "REG9") (pin "3") (pinfunction "GND_3") (pintype "passive"))
      (node (ref "REG9") (pin "6") (pinfunction "GND_6") (pintype "passive"))
      (node (ref "REG9") (pin "7") (pinfunction "GND_7") (pintype "passive"))
      (node (ref "TP2") (pin "1") (pinfunction "TP_1") (pintype "passive"))
    )
    (net (code "17") (name "/OUT1A") (class "Default")
      (node (ref "R341") (pin "2") (pinfunction "2_2") (pintype "passive"))
      (node (ref "REG13") (pin "10") (pinfunction "OUT_10") (pintype "passive"))
      (node (ref "REG13") (pin "11") (pinfunction "OUT_11") (pintype "passive"))
      (node (ref "REG13") (pin "12") (pinfunction "OUT_12") (pintype "passive"))
    )
    (net (code "18") (name "/OUT1B") (class "Default")
      (node (ref "R345") (pin "2") (pinfunction "2_2") (pintype "passive"))
      (node (ref "REG19") (pin "10") (pinfunction "OUT_10") (pintype "passive"))
      (node (ref "REG19") (pin "11") (pinfunction "OUT_11") (pintype "passive"))
      (node (ref "REG19") (pin "12") (pinfunction "OUT_12") (pintype "passive"))
    )
    (net (code "19") (name "/OUT2A") (class "Default")
      (node (ref "R342") (pin "2") (pinfunction "2_2") (pintype "passive"))
      (node (ref "REG14") (pin "10") (pinfunction "OUT_10") (pintype "passive"))
      (node (ref "REG14") (pin "11") (pinfunction "OUT_11") (pintype "passive"))
      (node (ref "REG14") (pin "12") (pinfunction "OUT_12") (pintype "passive"))
    )
    (net (code "20") (name "/OUT2B") (class "Default")
      (node (ref "R346") (pin "2") (pinfunction "2_2") (pintype "passive"))
      (node (ref "REG20") (pin "10") (pinfunction "OUT_10") (pintype "passive"))
      (node (ref "REG20") (pin "11") (pinfunction "OUT_11") (pintype "passive"))
      (node (ref "REG20") (pin "12") (pinfunction "OUT_12") (pintype "passive"))
    )
    (net (code "21") (name "/OUT3A") (class "Default")
      (node (ref "R343") (pin "2") (pinfunction "2_2") (pintype "passive"))
      (node (ref "REG15") (pin "10") (pinfunction "OUT_10") (pintype "passive"))
      (node (ref "REG15") (pin "11") (pinfunction "OUT_11") (pintype "passive"))
      (node (ref "REG15") (pin "12") (pinfunction "OUT_12") (pintype "passive"))
    )
    (net (code "22") (name "/OUT3B") (class "Default")
      (node (ref "R347") (pin "2") (pinfunction "2_2") (pintype "passive"))
      (node (ref "REG21") (pin "10") (pinfunction "OUT_10") (pintype "passive"))
      (node (ref "REG21") (pin "11") (pinfunction "OUT_11") (pintype "passive"))
      (node (ref "REG21") (pin "12") (pinfunction "OUT_12") (pintype "passive"))
    )
    (net (code "23") (name "/OUT4A") (class "Default")
      (node (ref "R344") (pin "2") (pinfunction "2_2") (pintype "passive"))
      (node (ref "REG16") (pin "10") (pinfunction "OUT_10") (pintype "passive"))
      (node (ref "REG16") (pin "11") (pinfunction "OUT_11") (pintype "passive"))
      (node (ref "REG16") (pin "12") (pinfunction "OUT_12") (pintype "passive"))
    )
    (net (code "24") (name "/OUT4B") (class "Default")
      (node (ref "R348") (pin "2") (pinfunction "2_2") (pintype "passive"))
      (node (ref "REG22") (pin "10") (pinfunction "OUT_10") (pintype "passive"))
      (node (ref "REG22") (pin "11") (pinfunction "OUT_11") (pintype "passive"))
      (node (ref "REG22") (pin "12") (pinfunction "OUT_12") (pintype "passive"))
    )
    (net (code "25") (name "/RON-5") (class "Default")
      (node (ref "R315") (pin "2") (pinfunction "2_2") (pintype "passive"))
      (node (ref "REG8") (pin "2") (pinfunction "RON_2") (pintype "passive"))
    )
    (net (code "26") (name "/RON5") (class "Default")
      (node (ref "R314") (pin "2") (pinfunction "2_2") (pintype "passive"))
      (node (ref "REG7") (pin "2") (pinfunction "RON_2") (pintype "passive"))
    )
    (net (code "27") (name "/RON15") (class "Default")
      (node (ref "R313") (pin "2") (pinfunction "2_2") (pintype "passive"))
      (node (ref "REG6") (pin "2") (pinfunction "RON_2") (pintype "passive"))
    )
    (net (code "28") (name "/SET1") (class "Default")
      (node (ref "C122") (pin "2") (pinfunction "2_2") (pintype "passive"))
      (node (ref "POT3") (pin "1") (pinfunction "A_1") (pintype "passive"))
      (node (ref "REG13") (pin "8") (pinfunction "SET_8") (pintype "passive"))
      (node (ref "REG19") (pin "8") (pinfunction "SET_8") (pintype "passive"))
    )
    (net (code "29") (name "/SET2") (class "Default")
      (node (ref "C123") (pin "2") (pinfunction "2_2") (pintype "passive"))
      (node (ref "POT4") (pin "1") (pinfunction "A_1") (pintype "passive"))
      (node (ref "REG14") (pin "8") (pinfunction "SET_8") (pintype "passive"))
      (node (ref "REG20") (pin "8") (pinfunction "SET_8") (pintype "passive"))
    )
    (net (code "30") (name "/SET3") (class "Default")
      (node (ref "C124") (pin "2") (pinfunction "2_2") (pintype "passive"))
      (node (ref "POT5") (pin "1") (pinfunction "A_1") (pintype "passive"))
      (node (ref "REG15") (pin "8") (pinfunction "SET_8") (pintype "passive"))
      (node (ref "REG21") (pin "8") (pinfunction "SET_8") (pintype "passive"))
    )
    (net (code "31") (name "/SET4") (class "Default")
      (node (ref "C125") (pin "2") (pinfunction "2_2") (pintype "passive"))
      (node (ref "POT6") (pin "1") (pinfunction "A_1") (pintype "passive"))
      (node (ref "REG16") (pin "8") (pinfunction "SET_8") (pintype "passive"))
      (node (ref "REG22") (pin "8") (pinfunction "SET_8") (pintype "passive"))
    )
    (net (code "32") (name "/SET5") (class "Default")
      (node (ref "C126") (pin "2") (pinfunction "2_2") (pintype "passive"))
      (node (ref "POT1") (pin "1") (pinfunction "A_1") (pintype "passive"))
      (node (ref "REG17") (pin "8") (pinfunction "SET_8") (pintype "passive"))
    )
    (net (code "33") (name "/SET6") (class "Default")
      (node (ref "C127") (pin "2") (pinfunction "2_2") (pintype "passive"))
      (node (ref "POT2") (pin "1") (pinfunction "A_1") (pintype "passive"))
      (node (ref "REG18") (pin "8") (pinfunction "SET_8") (pintype "passive"))
    )
    (net (code "34") (name "/SS-5") (class "Default")
      (node (ref "C99") (pin "2") (pinfunction "2_2") (pintype "passive"))
      (node (ref "REG8") (pin "5") (pinfunction "SS_5") (pintype "passive"))
    )
    (net (code "35") (name "/SS5") (class "Default")
      (node (ref "C98") (pin "2") (pinfunction "2_2") (pintype "passive"))
      (node (ref "REG7") (pin "5") (pinfunction "SS_5") (pintype "passive"))
    )
    (net (code "36") (name "/SS15") (class "Default")
      (node (ref "C97") (pin "2") (pinfunction "2_2") (pintype "passive"))
      (node (ref "REG6") (pin "5") (pinfunction "SS_5") (pintype "passive"))
    )
    (net (code "37") (name "/VN1") (class "Default")
      (node (ref "C134") (pin "1") (pinfunction "1_1") (pintype "passive"))
      (node (ref "R341") (pin "1") (pinfunction "1_1") (pintype "passive"))
      (node (ref "R345") (pin "1") (pinfunction "1_1") (pintype "passive"))
    )
    (net (code "38") (name "/VN2") (class "Default")
      (node (ref "C135") (pin "1") (pinfunction "1_1") (pintype "passive"))
      (node (ref "R342") (pin "1") (pinfunction "1_1") (pintype "passive"))
      (node (ref "R346") (pin "1") (pinfunction "1_1") (pintype "passive"))
      (node (ref "TP50") (pin "1") (pinfunction "TP_1") (pintype "passive"))
    )
    (net (code "39") (name "/VN3") (class "Default")
      (node (ref "C136") (pin "1") (pinfunction "1_1") (pintype "passive"))
      (node (ref "R343") (pin "1") (pinfunction "1_1") (pintype "passive"))
      (node (ref "R347") (pin "1") (pinfunction "1_1") (pintype "passive"))
      (node (ref "TP51") (pin "1") (pinfunction "TP_1") (pintype "passive"))
    )
    (net (code "40") (name "/VN4") (class "Default")
      (node (ref "C137") (pin "1") (pinfunction "1_1") (pintype "passive"))
      (node (ref "R344") (pin "1") (pinfunction "1_1") (pintype "passive"))
      (node (ref "R348") (pin "1") (pinfunction "1_1") (pintype "passive"))
      (node (ref "TP52") (pin "1") (pinfunction "TP_1") (pintype "passive"))
    )
    (net (code "41") (name "/VN5") (class "Default")
      (node (ref "C132") (pin "1") (pinfunction "1_1") (pintype "passive"))
      (node (ref "REG17") (pin "10") (pinfunction "OUT_10") (pintype "passive"))
      (node (ref "REG17") (pin "11") (pinfunction "OUT_11") (pintype "passive"))
      (node (ref "REG17") (pin "12") (pinfunction "OUT_12") (pintype "passive"))
      (node (ref "TP47") (pin "1") (pinfunction "TP_1") (pintype "passive"))
    )
    (net (code "42") (name "/VN6") (class "Default")
      (node (ref "C133") (pin "1") (pinfunction "1_1") (pintype "passive"))
      (node (ref "REG18") (pin "10") (pinfunction "OUT_10") (pintype "passive"))
      (node (ref "REG18") (pin "11") (pinfunction "OUT_11") (pintype "passive"))
      (node (ref "REG18") (pin "12") (pinfunction "OUT_12") (pintype "passive"))
      (node (ref "TP48") (pin "1") (pinfunction "TP_1") (pintype "passive"))
    )
    (net (code "44") (name "Net-(LED-5V-Pad1)") (class "Default")
      (node (ref "LED-5V") (pin "1") (pinfunction "1_1") (pintype "passive"))
      (node (ref "R327") (pin "2") (pinfunction "2_2") (pintype "passive"))
    )
    (net (code "45") (name "Net-(LED5V-Pad1)") (class "Default")
      (node (ref "LED5V") (pin "1") (pinfunction "1_1") (pintype "passive"))
      (node (ref "R323") (pin "2") (pinfunction "2_2") (pintype "passive"))
    )
    (net (code "46") (name "Net-(LED15V-Pad1)") (class "Default")
      (node (ref "LED15V") (pin "1") (pinfunction "1_1") (pintype "passive"))
      (node (ref "R316") (pin "2") (pinfunction "2_2") (pintype "passive"))
    )
    (net (code "47") (name "Net-(LED24V-Pad1)") (class "Default")
      (node (ref "LED24V") (pin "1") (pinfunction "1_1") (pintype "passive"))
      (node (ref "R312") (pin "2") (pinfunction "2_2") (pintype "passive"))
    )
    (net (code "48") (name "Net-(REG13-ILIM)") (class "Default")
      (node (ref "R331") (pin "1") (pinfunction "1_1") (pintype "passive"))
      (node (ref "REG13") (pin "4") (pinfunction "ILIM_4") (pintype "passive"))
    )
    (net (code "49") (name "Net-(REG14-ILIM)") (class "Default")
      (node (ref "R332") (pin "1") (pinfunction "1_1") (pintype "passive"))
      (node (ref "REG14") (pin "4") (pinfunction "ILIM_4") (pintype "passive"))
    )
    (net (code "50") (name "Net-(REG15-ILIM)") (class "Default")
      (node (ref "R333") (pin "1") (pinfunction "1_1") (pintype "passive"))
      (node (ref "REG15") (pin "4") (pinfunction "ILIM_4") (pintype "passive"))
    )
    (net (code "51") (name "Net-(REG16-ILIM)") (class "Default")
      (node (ref "R334") (pin "1") (pinfunction "1_1") (pintype "passive"))
      (node (ref "REG16") (pin "4") (pinfunction "ILIM_4") (pintype "passive"))
    )
    (net (code "52") (name "Net-(REG17-ILIM)") (class "Default")
      (node (ref "R335") (pin "1") (pinfunction "1_1") (pintype "passive"))
      (node (ref "REG17") (pin "4") (pinfunction "ILIM_4") (pintype "passive"))
    )
    (net (code "53") (name "Net-(REG18-ILIM)") (class "Default")
      (node (ref "R336") (pin "1") (pinfunction "1_1") (pintype "passive"))
      (node (ref "REG18") (pin "4") (pinfunction "ILIM_4") (pintype "passive"))
    )
    (net (code "54") (name "Net-(REG19-ILIM)") (class "Default")
      (node (ref "R337") (pin "1") (pinfunction "1_1") (pintype "passive"))
      (node (ref "REG19") (pin "4") (pinfunction "ILIM_4") (pintype "passive"))
    )
    (net (code "55") (name "Net-(REG20-ILIM)") (class "Default")
      (node (ref "R338") (pin "1") (pinfunction "1_1") (pintype "passive"))
      (node (ref "REG20") (pin "4") (pinfunction "ILIM_4") (pintype "passive"))
    )
    (net (code "56") (name "Net-(REG21-ILIM)") (class "Default")
      (node (ref "R339") (pin "1") (pinfunction "1_1") (pintype "passive"))
      (node (ref "REG21") (pin "4") (pinfunction "ILIM_4") (pintype "passive"))
    )
    (net (code "57") (name "Net-(REG22-ILIM)") (class "Default")
      (node (ref "R340") (pin "1") (pinfunction "1_1") (pintype "passive"))
      (node (ref "REG22") (pin "4") (pinfunction "ILIM_4") (pintype "passive"))
    )
    (net (code "58") (name "unconnected-(POT1-B-Pad3)") (class "Default")
      (node (ref "POT1") (pin "3") (pinfunction "B_3") (pintype "passive+no_connect"))
    )
    (net (code "59") (name "unconnected-(POT2-B-Pad3)") (class "Default")
      (node (ref "POT2") (pin "3") (pinfunction "B_3") (pintype "passive+no_connect"))
    )
    (net (code "60") (name "unconnected-(POT3-B-Pad3)") (class "Default")
      (node (ref "POT3") (pin "3") (pinfunction "B_3") (pintype "passive+no_connect"))
    )
    (net (code "61") (name "unconnected-(POT4-B-Pad3)") (class "Default")
      (node (ref "POT4") (pin "3") (pinfunction "B_3") (pintype "passive+no_connect"))
    )
    (net (code "62") (name "unconnected-(POT5-B-Pad3)") (class "Default")
      (node (ref "POT5") (pin "3") (pinfunction "B_3") (pintype "passive+no_connect"))
    )
    (net (code "63") (name "unconnected-(POT6-B-Pad3)") (class "Default")
      (node (ref "POT6") (pin "3") (pinfunction "B_3") (pintype "passive+no_connect"))
    )
    (net (code "64") (name "unconnected-(REG9-NC-Pad4)") (class "Default")
      (node (ref "REG9") (pin "4") (pinfunction "NC_4") (pintype "passive+no_connect"))
    )
    (net (code "65") (name "unconnected-(REG10-NC-Pad4)") (class "Default")
      (node (ref "REG10") (pin "4") (pinfunction "NC_4") (pintype "passive+no_connect"))
    )
    (net (code "66") (name "unconnected-(REG11-NC-Pad6)") (class "Default")
      (node (ref "REG11") (pin "6") (pinfunction "NC_6") (pintype "passive+no_connect"))
    )
    (net (code "67") (name "unconnected-(REG12-NC-Pad2)") (class "Default")
      (node (ref "REG12") (pin "2") (pinfunction "NC_2") (pintype "passive+no_connect"))
    )
    (net (code "68") (name "unconnected-(REG12-NC-Pad7)") (class "Default")
      (node (ref "REG12") (pin "7") (pinfunction "NC_7") (pintype "passive+no_connect"))
    )
  )
)
